# audio_channel.net
KiCad netlist of a schematic drawn in EasyEDA
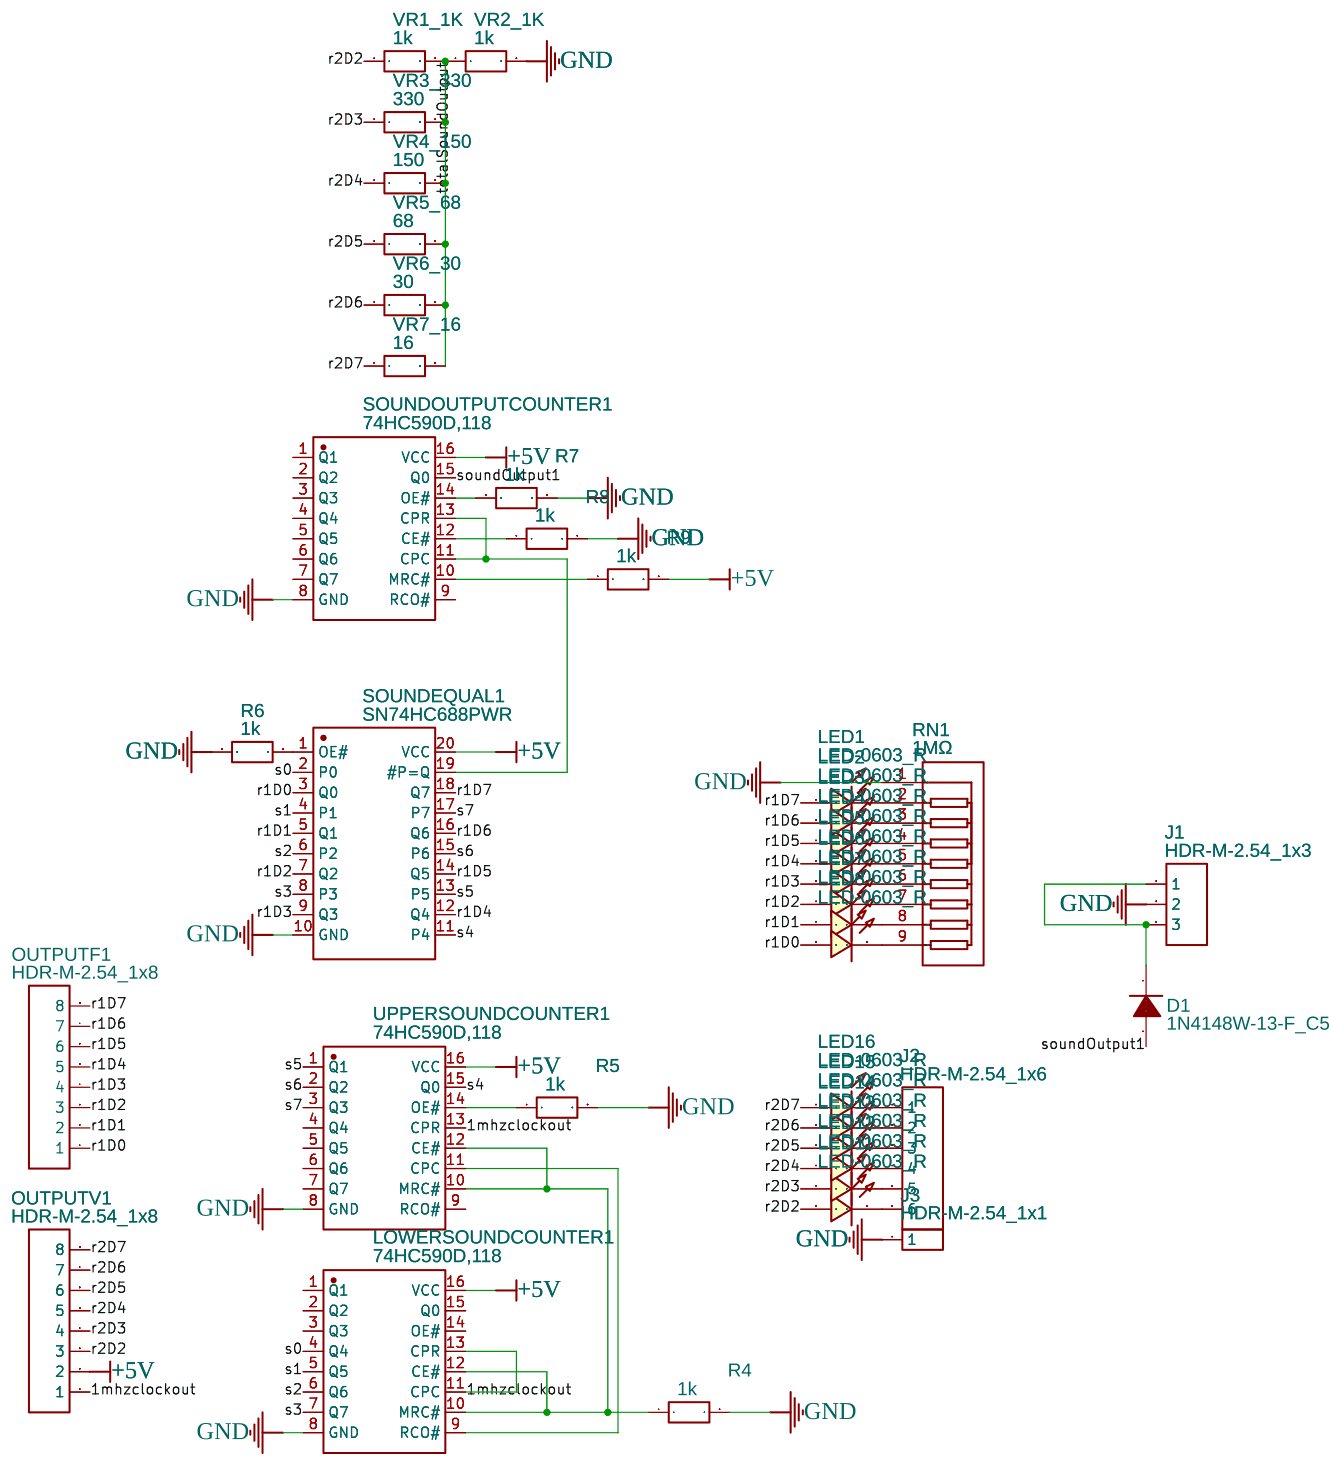
[diagram p0: schematic sheet]

(export (version "E")
  (design (tool "Eeschema 10.0.6"))
  (components
    (comp (ref "D1")
      (value "1N4148W-13-F_C526199")
      (fields
        (field (name "Manufacturer Part") "1N4148W-13-F")
        (field (name "Manufacturer") "Diodes Incorporated")
      )
      (libsource (lib "") (part "1N4148W-13-F_C526199"))
    )
    (comp (ref "J1") (value "HDR-M-2.54_1x3") (libsource (lib "") (part "HDR-M-2.54_1x3")))
    (comp (ref "J2")
      (value "HDR-M-2.54_1x6")
      (fields (field (name "BOM_Supplier Part") "C190819"))
      (libsource (lib "") (part "HDR-M-2.54_1x6"))
    )
    (comp (ref "J3")
      (value "HDR-M-2.54_1x1")
      (fields (field (name "BOM_Supplier Part") "C81276"))
      (libsource (lib "") (part "HDR-M-2.54_1x1"))
    )
    (comp (ref "LED1")
      (value "LED-0603_R")
      (fields
        (field (name "Manufacturer Part") "19-217/R6C-AL1M2VY/3T")
        (field (name "Manufacturer") "EVERLIGHT(台湾亿光)")
      )
      (libsource (lib "") (part "LED-0603_R"))
    )
    (comp (ref "LED2")
      (value "LED-0603_R")
      (fields
        (field (name "Manufacturer Part") "19-217/R6C-AL1M2VY/3T")
        (field (name "Manufacturer") "EVERLIGHT(台湾亿光)")
      )
      (libsource (lib "") (part "LED-0603_R"))
    )
    (comp (ref "LED3")
      (value "LED-0603_R")
      (fields
        (field (name "Manufacturer Part") "19-217/R6C-AL1M2VY/3T")
        (field (name "Manufacturer") "EVERLIGHT(台湾亿光)")
      )
      (libsource (lib "") (part "LED-0603_R"))
    )
    (comp (ref "LED4")
      (value "LED-0603_R")
      (fields
        (field (name "Manufacturer Part") "19-217/R6C-AL1M2VY/3T")
        (field (name "Manufacturer") "EVERLIGHT(台湾亿光)")
      )
      (libsource (lib "") (part "LED-0603_R"))
    )
    (comp (ref "LED5")
      (value "LED-0603_R")
      (fields
        (field (name "Manufacturer Part") "19-217/R6C-AL1M2VY/3T")
        (field (name "Manufacturer") "EVERLIGHT(台湾亿光)")
      )
      (libsource (lib "") (part "LED-0603_R"))
    )
    (comp (ref "LED6")
      (value "LED-0603_R")
      (fields
        (field (name "Manufacturer Part") "19-217/R6C-AL1M2VY/3T")
        (field (name "Manufacturer") "EVERLIGHT(台湾亿光)")
      )
      (libsource (lib "") (part "LED-0603_R"))
    )
    (comp (ref "LED7")
      (value "LED-0603_R")
      (fields
        (field (name "Manufacturer Part") "19-217/R6C-AL1M2VY/3T")
        (field (name "Manufacturer") "EVERLIGHT(台湾亿光)")
      )
      (libsource (lib "") (part "LED-0603_R"))
    )
    (comp (ref "LED8")
      (value "LED-0603_R")
      (fields
        (field (name "Manufacturer Part") "19-217/R6C-AL1M2VY/3T")
        (field (name "Manufacturer") "EVERLIGHT(台湾亿光)")
      )
      (libsource (lib "") (part "LED-0603_R"))
    )
    (comp (ref "LED11")
      (value "LED-0603_R")
      (fields
        (field (name "Manufacturer Part") "19-217/R6C-AL1M2VY/3T")
        (field (name "Manufacturer") "EVERLIGHT(台湾亿光)")
      )
      (libsource (lib "") (part "LED-0603_R"))
    )
    (comp (ref "LED12")
      (value "LED-0603_R")
      (fields
        (field (name "Manufacturer Part") "19-217/R6C-AL1M2VY/3T")
        (field (name "Manufacturer") "EVERLIGHT(台湾亿光)")
      )
      (libsource (lib "") (part "LED-0603_R"))
    )
    (comp (ref "LED13")
      (value "LED-0603_R")
      (fields
        (field (name "Manufacturer Part") "19-217/R6C-AL1M2VY/3T")
        (field (name "Manufacturer") "EVERLIGHT(台湾亿光)")
      )
      (libsource (lib "") (part "LED-0603_R"))
    )
    (comp (ref "LED14")
      (value "LED-0603_R")
      (fields
        (field (name "Manufacturer Part") "19-217/R6C-AL1M2VY/3T")
        (field (name "Manufacturer") "EVERLIGHT(台湾亿光)")
      )
      (libsource (lib "") (part "LED-0603_R"))
    )
    (comp (ref "LED15")
      (value "LED-0603_R")
      (fields
        (field (name "Manufacturer Part") "19-217/R6C-AL1M2VY/3T")
        (field (name "Manufacturer") "EVERLIGHT(台湾亿光)")
      )
      (libsource (lib "") (part "LED-0603_R"))
    )
    (comp (ref "LED16")
      (value "LED-0603_R")
      (fields
        (field (name "Manufacturer Part") "19-217/R6C-AL1M2VY/3T")
        (field (name "Manufacturer") "EVERLIGHT(台湾亿光)")
      )
      (libsource (lib "") (part "LED-0603_R"))
    )
    (comp (ref "LOWERSOUNDCOUNTER1")
      (value "74HC590D,118")
      (fields (field (name "Manufacturer") "Nexperia(安世)"))
      (libsource (lib "") (part "74HC590D,118_2"))
    )
    (comp (ref "OUTPUTF1") (value "HDR-M-2.54_1x8") (libsource (lib "") (part "HDR-M-2.54_1x8")))
    (comp (ref "OUTPUTV1") (value "HDR-M-2.54_1x8") (libsource (lib "") (part "HDR-M-2.54_1x8_1")))
    (comp (ref "R4") (value "1k") (libsource (lib "") (part "R_1206_EU")))
    (comp (ref "R5") (value "1k") (libsource (lib "") (part "R_1206_EU")))
    (comp (ref "R6") (value "1k") (libsource (lib "") (part "R_1206_EU")))
    (comp (ref "R7") (value "1k") (libsource (lib "") (part "R_1206_EU")))
    (comp (ref "R8") (value "1k") (libsource (lib "") (part "R_1206_EU")))
    (comp (ref "R9") (value "1k") (libsource (lib "") (part "R_1206_EU")))
    (comp (ref "RN1")
      (value "1MΩ")
      (fields (field (name "Manufacturer Part") "4609X-101-105LF") (field (name "Manufacturer") "BOURNS"))
      (libsource (lib "") (part "4609X-101-105LF"))
    )
    (comp (ref "SOUNDEQUAL1")
      (value "SN74HC688PWR")
      (fields (field (name "Manufacturer") "TI(德州仪器)"))
      (libsource (lib "") (part "SN74HC688PWR"))
    )
    (comp (ref "SOUNDOUTPUTCOUNTER1")
      (value "74HC590D,118")
      (fields (field (name "Manufacturer") "Nexperia(安世)"))
      (libsource (lib "") (part "74HC590D,118_1"))
    )
    (comp (ref "UPPERSOUNDCOUNTER1")
      (value "74HC590D,118")
      (fields (field (name "Manufacturer") "Nexperia(安世)"))
      (libsource (lib "") (part "74HC590D,118"))
    )
    (comp (ref "VR1_1K") (value "1k") (libsource (lib "") (part "R_1206_EU_2")))
    (comp (ref "VR2_1K") (value "1k") (libsource (lib "") (part "R_1206_EU_4")))
    (comp (ref "VR3_330") (value "330") (libsource (lib "") (part "R_1206_EU_1")))
    (comp (ref "VR4_150") (value "150") (libsource (lib "") (part "R_1206_EU_7")))
    (comp (ref "VR5_68") (value "68") (libsource (lib "") (part "R_1206_EU_5")))
    (comp (ref "VR6_30") (value "30") (libsource (lib "") (part "R_1206_EU_6")))
    (comp (ref "VR7_16") (value "16") (libsource (lib "") (part "R_1206_EU_3")))
  )
  (nets
    (net (code "1") (name "+5V") (class "Default")
      (node (ref "LOWERSOUNDCOUNTER1") (pin "16") (pinfunction "VCC_16") (pintype "unspecified"))
      (node (ref "OUTPUTV1") (pin "2") (pinfunction "2_2") (pintype "unspecified"))
      (node (ref "R9") (pin "2") (pinfunction "2_2") (pintype "unspecified"))
      (node (ref "SOUNDEQUAL1") (pin "20") (pinfunction "VCC_20") (pintype "unspecified"))
      (node (ref "SOUNDOUTPUTCOUNTER1") (pin "16") (pinfunction "VCC_16") (pintype "unspecified"))
      (node (ref "UPPERSOUNDCOUNTER1") (pin "16") (pinfunction "VCC_16") (pintype "unspecified"))
    )
    (net (code "2") (name "/1mhzclockout") (class "Default")
      (node (ref "LOWERSOUNDCOUNTER1") (pin "11") (pinfunction "CPC_11") (pintype "unspecified"))
      (node (ref "LOWERSOUNDCOUNTER1") (pin "13") (pinfunction "CPR_13") (pintype "unspecified"))
      (node (ref "OUTPUTV1") (pin "1") (pinfunction "1_1") (pintype "unspecified"))
      (node (ref "UPPERSOUNDCOUNTER1") (pin "13") (pinfunction "CPR_13") (pintype "unspecified"))
    )
    (net (code "3") (name "/r1D0") (class "Default")
      (node (ref "LED8") (pin "1") (pinfunction "1_1") (pintype "unspecified"))
      (node (ref "OUTPUTF1") (pin "1") (pinfunction "1_1") (pintype "unspecified"))
      (node (ref "SOUNDEQUAL1") (pin "3") (pinfunction "Q0_3") (pintype "unspecified"))
    )
    (net (code "4") (name "/r1D1") (class "Default")
      (node (ref "LED7") (pin "1") (pinfunction "1_1") (pintype "unspecified"))
      (node (ref "OUTPUTF1") (pin "2") (pinfunction "2_2") (pintype "unspecified"))
      (node (ref "SOUNDEQUAL1") (pin "5") (pinfunction "Q1_5") (pintype "unspecified"))
    )
    (net (code "5") (name "/r1D2") (class "Default")
      (node (ref "LED6") (pin "1") (pinfunction "1_1") (pintype "unspecified"))
      (node (ref "OUTPUTF1") (pin "3") (pinfunction "3_3") (pintype "unspecified"))
      (node (ref "SOUNDEQUAL1") (pin "7") (pinfunction "Q2_7") (pintype "unspecified"))
    )
    (net (code "6") (name "/r1D3") (class "Default")
      (node (ref "LED5") (pin "1") (pinfunction "1_1") (pintype "unspecified"))
      (node (ref "OUTPUTF1") (pin "4") (pinfunction "4_4") (pintype "unspecified"))
      (node (ref "SOUNDEQUAL1") (pin "9") (pinfunction "Q3_9") (pintype "unspecified"))
    )
    (net (code "7") (name "/r1D4") (class "Default")
      (node (ref "LED4") (pin "1") (pinfunction "1_1") (pintype "unspecified"))
      (node (ref "OUTPUTF1") (pin "5") (pinfunction "5_5") (pintype "unspecified"))
      (node (ref "SOUNDEQUAL1") (pin "12") (pinfunction "Q4_12") (pintype "unspecified"))
    )
    (net (code "8") (name "/r1D5") (class "Default")
      (node (ref "LED3") (pin "1") (pinfunction "1_1") (pintype "unspecified"))
      (node (ref "OUTPUTF1") (pin "6") (pinfunction "6_6") (pintype "unspecified"))
      (node (ref "SOUNDEQUAL1") (pin "14") (pinfunction "Q5_14") (pintype "unspecified"))
    )
    (net (code "9") (name "/r1D6") (class "Default")
      (node (ref "LED2") (pin "1") (pinfunction "1_1") (pintype "unspecified"))
      (node (ref "OUTPUTF1") (pin "7") (pinfunction "7_7") (pintype "unspecified"))
      (node (ref "SOUNDEQUAL1") (pin "16") (pinfunction "Q6_16") (pintype "unspecified"))
    )
    (net (code "10") (name "/r1D7") (class "Default")
      (node (ref "LED1") (pin "1") (pinfunction "1_1") (pintype "unspecified"))
      (node (ref "OUTPUTF1") (pin "8") (pinfunction "8_8") (pintype "unspecified"))
      (node (ref "SOUNDEQUAL1") (pin "18") (pinfunction "Q7_18") (pintype "unspecified"))
    )
    (net (code "11") (name "/r2D2") (class "Default")
      (node (ref "LED11") (pin "1") (pinfunction "1_1") (pintype "unspecified"))
      (node (ref "OUTPUTV1") (pin "3") (pinfunction "3_3") (pintype "unspecified"))
      (node (ref "VR1_1K") (pin "1") (pinfunction "1_1") (pintype "unspecified"))
    )
    (net (code "12") (name "/r2D3") (class "Default")
      (node (ref "LED12") (pin "1") (pinfunction "1_1") (pintype "unspecified"))
      (node (ref "OUTPUTV1") (pin "4") (pinfunction "4_4") (pintype "unspecified"))
      (node (ref "VR3_330") (pin "1") (pinfunction "1_1") (pintype "unspecified"))
    )
    (net (code "13") (name "/r2D4") (class "Default")
      (node (ref "LED13") (pin "1") (pinfunction "1_1") (pintype "unspecified"))
      (node (ref "OUTPUTV1") (pin "5") (pinfunction "5_5") (pintype "unspecified"))
      (node (ref "VR4_150") (pin "1") (pinfunction "1_1") (pintype "unspecified"))
    )
    (net (code "14") (name "/r2D5") (class "Default")
      (node (ref "LED14") (pin "1") (pinfunction "1_1") (pintype "unspecified"))
      (node (ref "OUTPUTV1") (pin "6") (pinfunction "6_6") (pintype "unspecified"))
      (node (ref "VR5_68") (pin "1") (pinfunction "1_1") (pintype "unspecified"))
    )
    (net (code "15") (name "/r2D6") (class "Default")
      (node (ref "LED15") (pin "1") (pinfunction "1_1") (pintype "unspecified"))
      (node (ref "OUTPUTV1") (pin "7") (pinfunction "7_7") (pintype "unspecified"))
      (node (ref "VR6_30") (pin "1") (pinfunction "1_1") (pintype "unspecified"))
    )
    (net (code "16") (name "/r2D7") (class "Default")
      (node (ref "LED16") (pin "1") (pinfunction "1_1") (pintype "unspecified"))
      (node (ref "OUTPUTV1") (pin "8") (pinfunction "8_8") (pintype "unspecified"))
      (node (ref "VR7_16") (pin "1") (pinfunction "1_1") (pintype "unspecified"))
    )
    (net (code "17") (name "/s0") (class "Default")
      (node (ref "LOWERSOUNDCOUNTER1") (pin "4") (pinfunction "Q4_4") (pintype "unspecified"))
      (node (ref "SOUNDEQUAL1") (pin "2") (pinfunction "P0_2") (pintype "unspecified"))
    )
    (net (code "18") (name "/s1") (class "Default")
      (node (ref "LOWERSOUNDCOUNTER1") (pin "5") (pinfunction "Q5_5") (pintype "unspecified"))
      (node (ref "SOUNDEQUAL1") (pin "4") (pinfunction "P1_4") (pintype "unspecified"))
    )
    (net (code "19") (name "/s2") (class "Default")
      (node (ref "LOWERSOUNDCOUNTER1") (pin "6") (pinfunction "Q6_6") (pintype "unspecified"))
      (node (ref "SOUNDEQUAL1") (pin "6") (pinfunction "P2_6") (pintype "unspecified"))
    )
    (net (code "20") (name "/s3") (class "Default")
      (node (ref "LOWERSOUNDCOUNTER1") (pin "7") (pinfunction "Q7_7") (pintype "unspecified"))
      (node (ref "SOUNDEQUAL1") (pin "8") (pinfunction "P3_8") (pintype "unspecified"))
    )
    (net (code "21") (name "/s4") (class "Default")
      (node (ref "SOUNDEQUAL1") (pin "11") (pinfunction "P4_11") (pintype "unspecified"))
      (node (ref "UPPERSOUNDCOUNTER1") (pin "15") (pinfunction "Q0_15") (pintype "unspecified"))
    )
    (net (code "22") (name "/s5") (class "Default")
      (node (ref "SOUNDEQUAL1") (pin "13") (pinfunction "P5_13") (pintype "unspecified"))
      (node (ref "UPPERSOUNDCOUNTER1") (pin "1") (pinfunction "Q1_1") (pintype "unspecified"))
    )
    (net (code "23") (name "/s6") (class "Default")
      (node (ref "SOUNDEQUAL1") (pin "15") (pinfunction "P6_15") (pintype "unspecified"))
      (node (ref "UPPERSOUNDCOUNTER1") (pin "2") (pinfunction "Q2_2") (pintype "unspecified"))
    )
    (net (code "24") (name "/s7") (class "Default")
      (node (ref "SOUNDEQUAL1") (pin "17") (pinfunction "P7_17") (pintype "unspecified"))
      (node (ref "UPPERSOUNDCOUNTER1") (pin "3") (pinfunction "Q3_3") (pintype "unspecified"))
    )
    (net (code "25") (name "/soundOutput1") (class "Default")
      (node (ref "D1") (pin "2") (pinfunction "+_2") (pintype "unspecified"))
      (node (ref "SOUNDOUTPUTCOUNTER1") (pin "15") (pinfunction "Q0_15") (pintype "unspecified"))
    )
    (net (code "26") (name "/totalSoundOutput") (class "Default")
      (node (ref "VR1_1K") (pin "2") (pinfunction "2_2") (pintype "unspecified"))
      (node (ref "VR2_1K") (pin "1") (pinfunction "1_1") (pintype "unspecified"))
      (node (ref "VR3_330") (pin "2") (pinfunction "2_2") (pintype "unspecified"))
      (node (ref "VR4_150") (pin "2") (pinfunction "2_2") (pintype "unspecified"))
      (node (ref "VR5_68") (pin "2") (pinfunction "2_2") (pintype "unspecified"))
      (node (ref "VR6_30") (pin "2") (pinfunction "2_2") (pintype "unspecified"))
      (node (ref "VR7_16") (pin "2") (pinfunction "2_2") (pintype "unspecified"))
    )
    (net (code "27") (name "GND") (class "Default")
      (node (ref "J1") (pin "2") (pinfunction "2_2") (pintype "input"))
      (node (ref "J3") (pin "1") (pinfunction "1_1") (pintype "input"))
      (node (ref "LOWERSOUNDCOUNTER1") (pin "8") (pinfunction "GND_8") (pintype "unspecified"))
      (node (ref "R4") (pin "2") (pinfunction "2_2") (pintype "unspecified"))
      (node (ref "R5") (pin "2") (pinfunction "2_2") (pintype "unspecified"))
      (node (ref "R6") (pin "1") (pinfunction "1_1") (pintype "unspecified"))
      (node (ref "R7") (pin "2") (pinfunction "2_2") (pintype "unspecified"))
      (node (ref "R8") (pin "2") (pinfunction "2_2") (pintype "unspecified"))
      (node (ref "RN1") (pin "1") (pinfunction "1_1") (pintype "input"))
      (node (ref "SOUNDEQUAL1") (pin "10") (pinfunction "GND_10") (pintype "unspecified"))
      (node (ref "SOUNDOUTPUTCOUNTER1") (pin "8") (pinfunction "GND_8") (pintype "unspecified"))
      (node (ref "UPPERSOUNDCOUNTER1") (pin "8") (pinfunction "GND_8") (pintype "unspecified"))
      (node (ref "VR2_1K") (pin "2") (pinfunction "2_2") (pintype "unspecified"))
    )
    (net (code "28") (name "Net-(D1--)") (class "Default")
      (node (ref "D1") (pin "1") (pinfunction "-_1") (pintype "unspecified"))
      (node (ref "J1") (pin "1") (pinfunction "1_1") (pintype "input"))
      (node (ref "J1") (pin "3") (pinfunction "3_3") (pintype "input"))
    )
    (net (code "29") (name "Net-(J2-Pad1)") (class "Default")
      (node (ref "J2") (pin "1") (pinfunction "1_1") (pintype "input"))
      (node (ref "LED16") (pin "2") (pinfunction "2_2") (pintype "unspecified"))
    )
    (net (code "30") (name "Net-(J2-Pad2)") (class "Default")
      (node (ref "J2") (pin "2") (pinfunction "2_2") (pintype "input"))
      (node (ref "LED15") (pin "2") (pinfunction "2_2") (pintype "unspecified"))
    )
    (net (code "31") (name "Net-(J2-Pad3)") (class "Default")
      (node (ref "J2") (pin "3") (pinfunction "3_3") (pintype "input"))
      (node (ref "LED14") (pin "2") (pinfunction "2_2") (pintype "unspecified"))
    )
    (net (code "32") (name "Net-(J2-Pad4)") (class "Default")
      (node (ref "J2") (pin "4") (pinfunction "4_4") (pintype "input"))
      (node (ref "LED13") (pin "2") (pinfunction "2_2") (pintype "unspecified"))
    )
    (net (code "33") (name "Net-(J2-Pad5)") (class "Default")
      (node (ref "J2") (pin "5") (pinfunction "5_5") (pintype "input"))
      (node (ref "LED12") (pin "2") (pinfunction "2_2") (pintype "unspecified"))
    )
    (net (code "34") (name "Net-(J2-Pad6)") (class "Default")
      (node (ref "J2") (pin "6") (pinfunction "6_6") (pintype "input"))
      (node (ref "LED11") (pin "2") (pinfunction "2_2") (pintype "unspecified"))
    )
    (net (code "35") (name "Net-(LED1-Pad2)") (class "Default")
      (node (ref "LED1") (pin "2") (pinfunction "2_2") (pintype "unspecified"))
      (node (ref "RN1") (pin "2") (pinfunction "2_2") (pintype "input"))
    )
    (net (code "36") (name "Net-(LED2-Pad2)") (class "Default")
      (node (ref "LED2") (pin "2") (pinfunction "2_2") (pintype "unspecified"))
      (node (ref "RN1") (pin "3") (pinfunction "3_3") (pintype "input"))
    )
    (net (code "37") (name "Net-(LED3-Pad2)") (class "Default")
      (node (ref "LED3") (pin "2") (pinfunction "2_2") (pintype "unspecified"))
      (node (ref "RN1") (pin "4") (pinfunction "4_4") (pintype "input"))
    )
    (net (code "38") (name "Net-(LED4-Pad2)") (class "Default")
      (node (ref "LED4") (pin "2") (pinfunction "2_2") (pintype "unspecified"))
      (node (ref "RN1") (pin "5") (pinfunction "5_5") (pintype "input"))
    )
    (net (code "39") (name "Net-(LED5-Pad2)") (class "Default")
      (node (ref "LED5") (pin "2") (pinfunction "2_2") (pintype "unspecified"))
      (node (ref "RN1") (pin "6") (pinfunction "6_6") (pintype "input"))
    )
    (net (code "40") (name "Net-(LED6-Pad2)") (class "Default")
      (node (ref "LED6") (pin "2") (pinfunction "2_2") (pintype "unspecified"))
      (node (ref "RN1") (pin "7") (pinfunction "7_7") (pintype "input"))
    )
    (net (code "41") (name "Net-(LED7-Pad2)") (class "Default")
      (node (ref "LED7") (pin "2") (pinfunction "2_2") (pintype "unspecified"))
      (node (ref "RN1") (pin "8") (pinfunction "8_8") (pintype "input"))
    )
    (net (code "42") (name "Net-(LED8-Pad2)") (class "Default")
      (node (ref "LED8") (pin "2") (pinfunction "2_2") (pintype "unspecified"))
      (node (ref "RN1") (pin "9") (pinfunction "9_9") (pintype "input"))
    )
    (net (code "43") (name "Net-(LOWERSOUNDCOUNTER1-CE#)") (class "Default")
      (node (ref "LOWERSOUNDCOUNTER1") (pin "10") (pinfunction "MRC#_10") (pintype "unspecified"))
      (node (ref "LOWERSOUNDCOUNTER1") (pin "12") (pinfunction "CE#_12") (pintype "unspecified"))
      (node (ref "R4") (pin "1") (pinfunction "1_1") (pintype "unspecified"))
      (node (ref "UPPERSOUNDCOUNTER1") (pin "10") (pinfunction "MRC#_10") (pintype "unspecified"))
      (node (ref "UPPERSOUNDCOUNTER1") (pin "12") (pinfunction "CE#_12") (pintype "unspecified"))
    )
    (net (code "44") (name "Net-(LOWERSOUNDCOUNTER1-RCO#)") (class "Default")
      (node (ref "LOWERSOUNDCOUNTER1") (pin "9") (pinfunction "RCO#_9") (pintype "unspecified"))
      (node (ref "UPPERSOUNDCOUNTER1") (pin "11") (pinfunction "CPC_11") (pintype "unspecified"))
    )
    (net (code "45") (name "Net-(SOUNDEQUAL1-#P=Q)") (class "Default")
      (node (ref "SOUNDEQUAL1") (pin "19") (pinfunction "#P=Q_19") (pintype "unspecified"))
      (node (ref "SOUNDOUTPUTCOUNTER1") (pin "11") (pinfunction "CPC_11") (pintype "unspecified"))
      (node (ref "SOUNDOUTPUTCOUNTER1") (pin "13") (pinfunction "CPR_13") (pintype "unspecified"))
    )
    (net (code "46") (name "Net-(SOUNDEQUAL1-OE#)") (class "Default")
      (node (ref "R6") (pin "2") (pinfunction "2_2") (pintype "unspecified"))
      (node (ref "SOUNDEQUAL1") (pin "1") (pinfunction "OE#_1") (pintype "unspecified"))
    )
    (net (code "47") (name "Net-(SOUNDOUTPUTCOUNTER1-CE#)") (class "Default")
      (node (ref "R8") (pin "1") (pinfunction "1_1") (pintype "unspecified"))
      (node (ref "SOUNDOUTPUTCOUNTER1") (pin "12") (pinfunction "CE#_12") (pintype "unspecified"))
    )
    (net (code "48") (name "Net-(SOUNDOUTPUTCOUNTER1-MRC#)") (class "Default")
      (node (ref "R9") (pin "1") (pinfunction "1_1") (pintype "unspecified"))
      (node (ref "SOUNDOUTPUTCOUNTER1") (pin "10") (pinfunction "MRC#_10") (pintype "unspecified"))
    )
    (net (code "49") (name "Net-(SOUNDOUTPUTCOUNTER1-OE#)") (class "Default")
      (node (ref "R7") (pin "1") (pinfunction "1_1") (pintype "unspecified"))
      (node (ref "SOUNDOUTPUTCOUNTER1") (pin "14") (pinfunction "OE#_14") (pintype "unspecified"))
    )
    (net (code "50") (name "Net-(UPPERSOUNDCOUNTER1-OE#)") (class "Default")
      (node (ref "R5") (pin "1") (pinfunction "1_1") (pintype "unspecified"))
      (node (ref "UPPERSOUNDCOUNTER1") (pin "14") (pinfunction "OE#_14") (pintype "unspecified"))
    )
    (net (code "51") (name "unconnected-(LOWERSOUNDCOUNTER1-OE#-Pad14)") (class "Default")
      (node (ref "LOWERSOUNDCOUNTER1") (pin "14") (pinfunction "OE#_14") (pintype "unspecified"))
    )
    (net (code "52") (name "unconnected-(LOWERSOUNDCOUNTER1-Q0-Pad15)") (class "Default")
      (node (ref "LOWERSOUNDCOUNTER1") (pin "15") (pinfunction "Q0_15") (pintype "unspecified"))
    )
    (net (code "53") (name "unconnected-(LOWERSOUNDCOUNTER1-Q1-Pad1)") (class "Default")
      (node (ref "LOWERSOUNDCOUNTER1") (pin "1") (pinfunction "Q1_1") (pintype "unspecified"))
    )
    (net (code "54") (name "unconnected-(LOWERSOUNDCOUNTER1-Q2-Pad2)") (class "Default")
      (node (ref "LOWERSOUNDCOUNTER1") (pin "2") (pinfunction "Q2_2") (pintype "unspecified"))
    )
    (net (code "55") (name "unconnected-(LOWERSOUNDCOUNTER1-Q3-Pad3)") (class "Default")
      (node (ref "LOWERSOUNDCOUNTER1") (pin "3") (pinfunction "Q3_3") (pintype "unspecified"))
    )
    (net (code "56") (name "unconnected-(SOUNDOUTPUTCOUNTER1-Q1-Pad1)") (class "Default")
      (node (ref "SOUNDOUTPUTCOUNTER1") (pin "1") (pinfunction "Q1_1") (pintype "unspecified"))
    )
    (net (code "57") (name "unconnected-(SOUNDOUTPUTCOUNTER1-Q2-Pad2)") (class "Default")
      (node (ref "SOUNDOUTPUTCOUNTER1") (pin "2") (pinfunction "Q2_2") (pintype "unspecified"))
    )
    (net (code "58") (name "unconnected-(SOUNDOUTPUTCOUNTER1-Q3-Pad3)") (class "Default")
      (node (ref "SOUNDOUTPUTCOUNTER1") (pin "3") (pinfunction "Q3_3") (pintype "unspecified"))
    )
    (net (code "59") (name "unconnected-(SOUNDOUTPUTCOUNTER1-Q4-Pad4)") (class "Default")
      (node (ref "SOUNDOUTPUTCOUNTER1") (pin "4") (pinfunction "Q4_4") (pintype "unspecified"))
    )
    (net (code "60") (name "unconnected-(SOUNDOUTPUTCOUNTER1-Q5-Pad5)") (class "Default")
      (node (ref "SOUNDOUTPUTCOUNTER1") (pin "5") (pinfunction "Q5_5") (pintype "unspecified"))
    )
    (net (code "61") (name "unconnected-(SOUNDOUTPUTCOUNTER1-Q6-Pad6)") (class "Default")
      (node (ref "SOUNDOUTPUTCOUNTER1") (pin "6") (pinfunction "Q6_6") (pintype "unspecified"))
    )
    (net (code "62") (name "unconnected-(SOUNDOUTPUTCOUNTER1-Q7-Pad7)") (class "Default")
      (node (ref "SOUNDOUTPUTCOUNTER1") (pin "7") (pinfunction "Q7_7") (pintype "unspecified"))
    )
    (net (code "63") (name "unconnected-(SOUNDOUTPUTCOUNTER1-RCO#-Pad9)") (class "Default")
      (node (ref "SOUNDOUTPUTCOUNTER1") (pin "9") (pinfunction "RCO#_9") (pintype "unspecified"))
    )
    (net (code "64") (name "unconnected-(UPPERSOUNDCOUNTER1-Q4-Pad4)") (class "Default")
      (node (ref "UPPERSOUNDCOUNTER1") (pin "4") (pinfunction "Q4_4") (pintype "unspecified"))
    )
    (net (code "65") (name "unconnected-(UPPERSOUNDCOUNTER1-Q5-Pad5)") (class "Default")
      (node (ref "UPPERSOUNDCOUNTER1") (pin "5") (pinfunction "Q5_5") (pintype "unspecified"))
    )
    (net (code "66") (name "unconnected-(UPPERSOUNDCOUNTER1-Q6-Pad6)") (class "Default")
      (node (ref "UPPERSOUNDCOUNTER1") (pin "6") (pinfunction "Q6_6") (pintype "unspecified"))
    )
    (net (code "67") (name "unconnected-(UPPERSOUNDCOUNTER1-Q7-Pad7)") (class "Default")
      (node (ref "UPPERSOUNDCOUNTER1") (pin "7") (pinfunction "Q7_7") (pintype "unspecified"))
    )
    (net (code "68") (name "unconnected-(UPPERSOUNDCOUNTER1-RCO#-Pad9)") (class "Default")
      (node (ref "UPPERSOUNDCOUNTER1") (pin "9") (pinfunction "RCO#_9") (pintype "unspecified"))
    )
  )
)
